# Incubadora_huevos.net
KiCad netlist of a schematic drawn in EAGLE
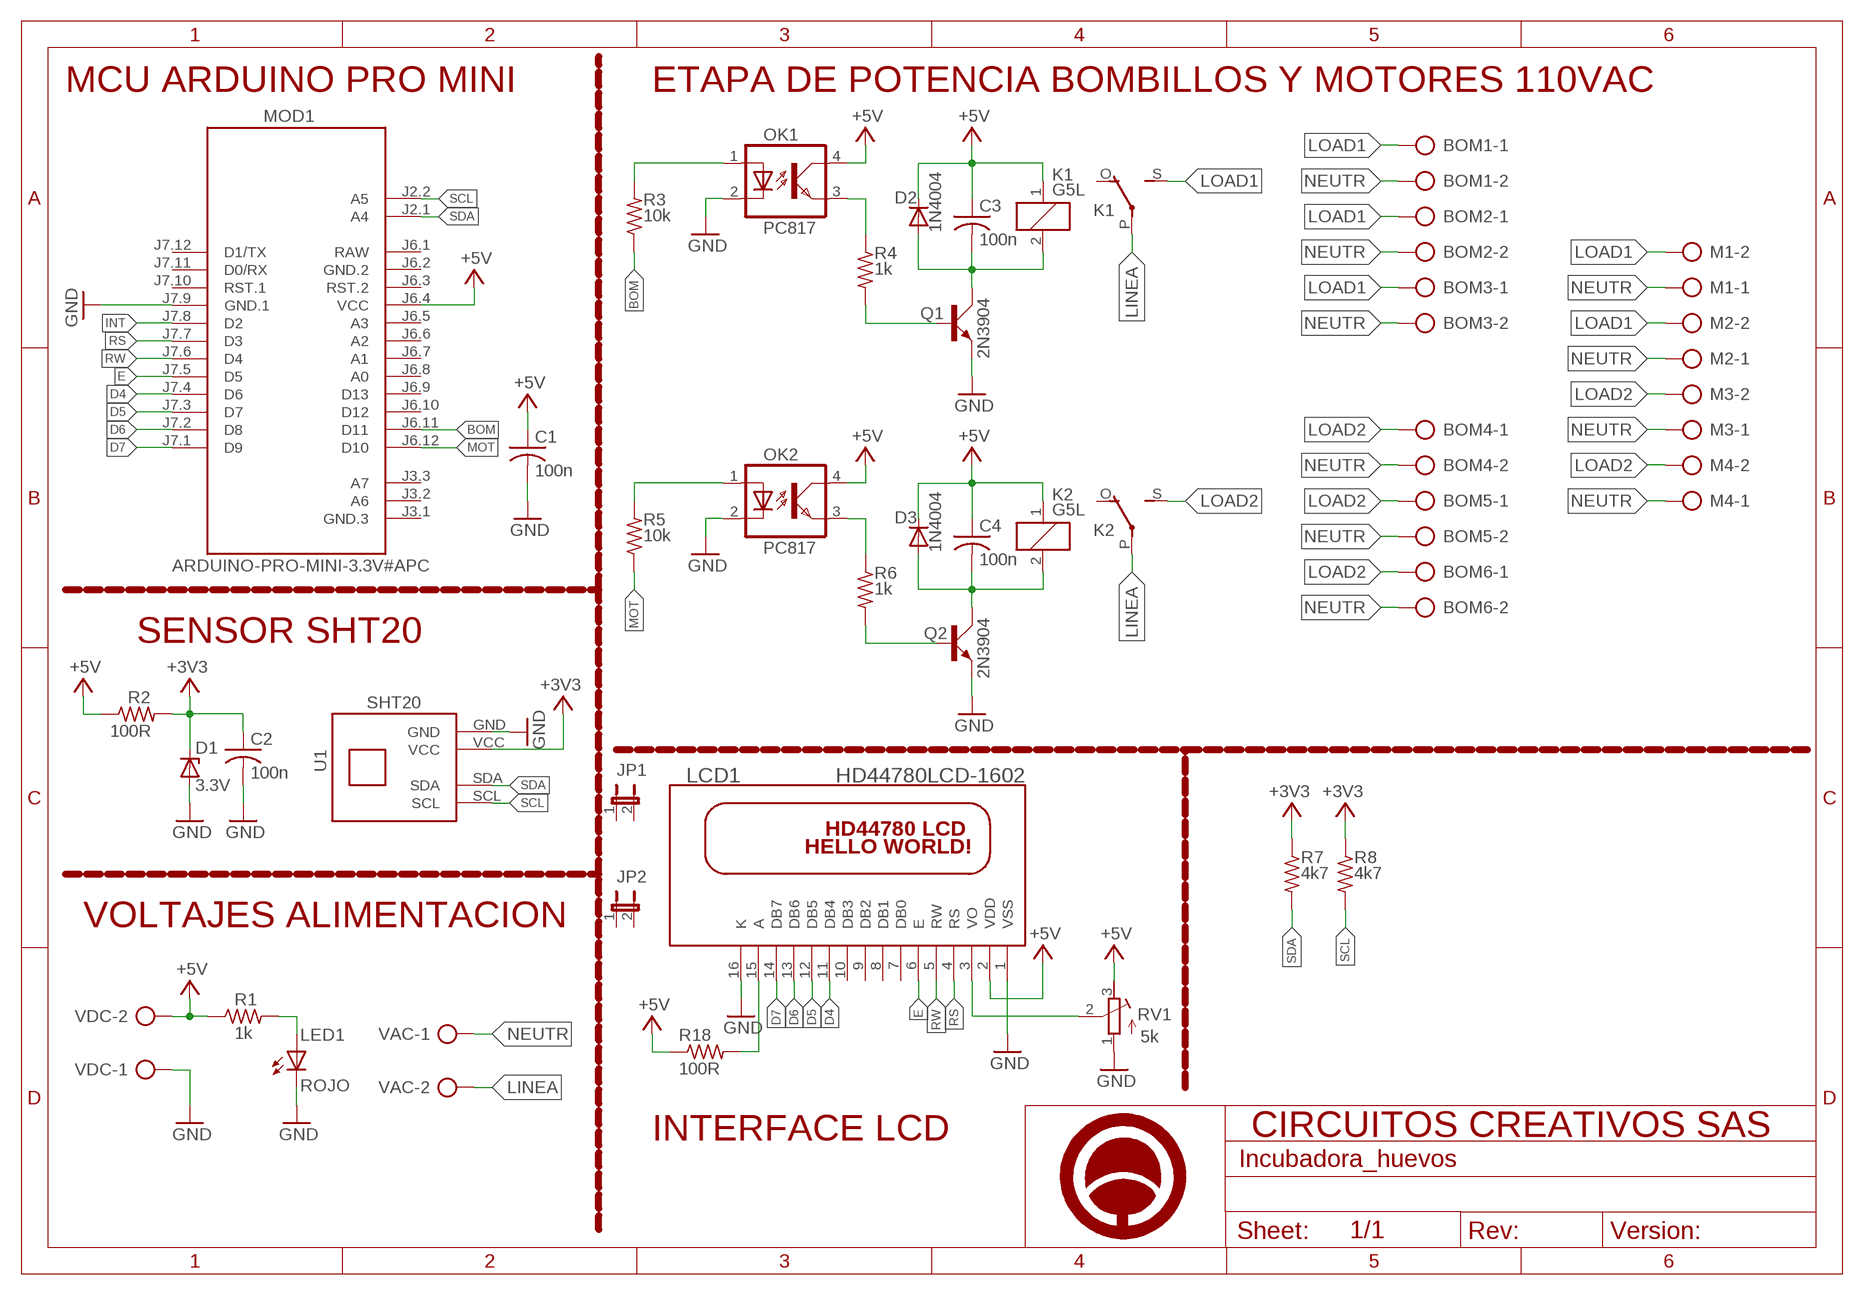
[diagram p0: schematic, sheet 1]

(export (version "E")
  (design (tool "Eeschema 10.0.6"))
  (components
    (comp (ref "BOM1")
      (value "AK500/2")
      (footprint "eagle-import:AK500_2")
      (libsource (lib "eagle-import") (part "AK500/2"))
    )
    (comp (ref "BOM2")
      (value "AK500/2")
      (footprint "eagle-import:AK500_2")
      (libsource (lib "eagle-import") (part "AK500/2"))
    )
    (comp (ref "BOM3")
      (value "AK500/2")
      (footprint "eagle-import:AK500_2")
      (libsource (lib "eagle-import") (part "AK500/2"))
    )
    (comp (ref "BOM4")
      (value "AK500/2")
      (footprint "eagle-import:AK500_2")
      (libsource (lib "eagle-import") (part "AK500/2"))
    )
    (comp (ref "BOM5")
      (value "AK500/2")
      (footprint "eagle-import:AK500_2")
      (libsource (lib "eagle-import") (part "AK500/2"))
    )
    (comp (ref "BOM6")
      (value "AK500/2")
      (footprint "eagle-import:AK500_2")
      (libsource (lib "eagle-import") (part "AK500/2"))
    )
    (comp (ref "C1")
      (value "100n")
      (footprint "eagle-import:C025-025X050")
      (libsource (lib "eagle-import") (part "C-US025-025X050"))
    )
    (comp (ref "C2")
      (value "100n")
      (footprint "eagle-import:C025-025X050")
      (libsource (lib "eagle-import") (part "C-US025-025X050"))
    )
    (comp (ref "C3")
      (value "100n")
      (footprint "eagle-import:C025-025X050")
      (libsource (lib "eagle-import") (part "C-US025-025X050"))
    )
    (comp (ref "C4")
      (value "100n")
      (footprint "eagle-import:C025-025X050")
      (libsource (lib "eagle-import") (part "C-US025-025X050"))
    )
    (comp (ref "D1")
      (value "3.3V")
      (footprint "eagle-import:DO41Z10")
      (libsource (lib "eagle-import") (part "ZENER-DIODEDO41Z10"))
    )
    (comp (ref "D2")
      (value "1N4004")
      (footprint "eagle-import:DO41-10")
      (libsource (lib "eagle-import") (part "1N4004"))
    )
    (comp (ref "D3")
      (value "1N4004")
      (footprint "eagle-import:DO41-10")
      (libsource (lib "eagle-import") (part "1N4004"))
    )
    (comp (ref "JP1")
      (value "JP1E")
      (footprint "eagle-import:JP1")
      (libsource (lib "eagle-import") (part "JP1E"))
    )
    (comp (ref "JP2")
      (value "JP1E")
      (footprint "eagle-import:JP1")
      (libsource (lib "eagle-import") (part "JP1E"))
    )
    (comp (ref "K1")
      (value "G5L")
      (footprint "eagle-import:G5LE")
      (libsource (lib "eagle-import") (part "G5L"))
    )
    (comp (ref "K2")
      (value "G5L")
      (footprint "eagle-import:G5LE")
      (libsource (lib "eagle-import") (part "G5L"))
    )
    (comp (ref "LCD1")
      (value "HD44780LCD-1602")
      (footprint "eagle-import:LCD1602")
      (libsource (lib "eagle-import") (part "HD44780LCD-1602"))
    )
    (comp (ref "LED1")
      (value "ROJO")
      (footprint "eagle-import:LED3MM")
      (libsource (lib "eagle-import") (part "LED3MM"))
    )
    (comp (ref "M1")
      (value "AK500/2")
      (footprint "eagle-import:AK500_2")
      (libsource (lib "eagle-import") (part "AK500/2"))
    )
    (comp (ref "M2")
      (value "AK500/2")
      (footprint "eagle-import:AK500_2")
      (libsource (lib "eagle-import") (part "AK500/2"))
    )
    (comp (ref "M3")
      (value "AK500/2")
      (footprint "eagle-import:AK500_2")
      (libsource (lib "eagle-import") (part "AK500/2"))
    )
    (comp (ref "M4")
      (value "AK500/2")
      (footprint "eagle-import:AK500_2")
      (libsource (lib "eagle-import") (part "AK500/2"))
    )
    (comp (ref "MOD1")
      (value "ARDUINO-PRO-MINI-3.3V#APC")
      (footprint "eagle-import:ARDUINO-PRO-MINI#APC")
      (libsource (lib "eagle-import") (part "ARDUINO-PRO-MINI-#APC3.3V"))
    )
    (comp (ref "OK1")
      (value "PC817")
      (footprint "eagle-import:DIL04")
      (fields (field (name "MPN") "PC817X4J000F"))
      (libsource (lib "eagle-import") (part "PC817"))
    )
    (comp (ref "OK2")
      (value "PC817")
      (footprint "eagle-import:DIL04")
      (fields (field (name "MPN") "PC817X4J000F"))
      (libsource (lib "eagle-import") (part "PC817"))
    )
    (comp (ref "Q1")
      (value "2N3904")
      (footprint "eagle-import:TO92D")
      (libsource (lib "eagle-import") (part "2N3904"))
    )
    (comp (ref "Q2")
      (value "2N3904")
      (footprint "eagle-import:TO92D")
      (libsource (lib "eagle-import") (part "2N3904"))
    )
    (comp (ref "R1")
      (value "1k")
      (footprint "eagle-import:0204_7")
      (libsource (lib "eagle-import") (part "R-US_0204/7"))
    )
    (comp (ref "R2")
      (value "100R")
      (footprint "eagle-import:0204_7")
      (libsource (lib "eagle-import") (part "R-US_0204/7"))
    )
    (comp (ref "R3")
      (value "10k")
      (footprint "eagle-import:0204_7")
      (libsource (lib "eagle-import") (part "R-US_0204/7"))
    )
    (comp (ref "R4")
      (value "1k")
      (footprint "eagle-import:0204_7")
      (libsource (lib "eagle-import") (part "R-US_0204/7"))
    )
    (comp (ref "R5")
      (value "10k")
      (footprint "eagle-import:0204_7")
      (libsource (lib "eagle-import") (part "R-US_0204/7"))
    )
    (comp (ref "R6")
      (value "1k")
      (footprint "eagle-import:0204_7")
      (libsource (lib "eagle-import") (part "R-US_0204/7"))
    )
    (comp (ref "R7")
      (value "4k7")
      (footprint "eagle-import:0204_7")
      (libsource (lib "eagle-import") (part "R-US_0204/7"))
    )
    (comp (ref "R8")
      (value "4k7")
      (footprint "eagle-import:0204_7")
      (libsource (lib "eagle-import") (part "R-US_0204/7"))
    )
    (comp (ref "R18")
      (value "100R")
      (footprint "eagle-import:0204_7")
      (libsource (lib "eagle-import") (part "R-US_0204/7"))
    )
    (comp (ref "RV1")
      (value "5k")
      (footprint "eagle-import:RTRIM3296W")
      (libsource (lib "eagle-import") (part "R-TRIMM3296W"))
    )
    (comp (ref "U$1")
      (value "A4_HORIZONTAL")
      (footprint "eagle-import:LOGO")
      (libsource (lib "eagle-import") (part "A4_HORIZONTAL"))
    )
    (comp (ref "U1")
      (value "SHT20")
      (footprint "eagle-import:SHT20")
      (libsource (lib "eagle-import") (part "SHT20"))
    )
    (comp (ref "VAC")
      (value "AK500/2")
      (footprint "eagle-import:AK500_2")
      (libsource (lib "eagle-import") (part "AK500/2"))
    )
    (comp (ref "VDC")
      (value "AK500/2")
      (footprint "eagle-import:AK500_2")
      (libsource (lib "eagle-import") (part "AK500/2"))
    )
  )
  (nets
    (net (code "1") (name "+3V3") (class "Default")
      (node (ref "C2") (pin "1") (pinfunction "1_1") (pintype "passive"))
      (node (ref "D1") (pin "C") (pinfunction "C_C") (pintype "passive"))
      (node (ref "R2") (pin "2") (pinfunction "2_2") (pintype "passive"))
      (node (ref "R7") (pin "1") (pinfunction "1_1") (pintype "passive"))
      (node (ref "R8") (pin "1") (pinfunction "1_1") (pintype "passive"))
      (node (ref "U1") (pin "VCC") (pinfunction "VCC_VCC") (pintype "power_in"))
    )
    (net (code "2") (name "+5V") (class "Default")
      (node (ref "C1") (pin "1") (pinfunction "1_1") (pintype "passive"))
      (node (ref "C3") (pin "1") (pinfunction "1_1") (pintype "passive"))
      (node (ref "C4") (pin "1") (pinfunction "1_1") (pintype "passive"))
      (node (ref "D2") (pin "C") (pinfunction "C_C") (pintype "passive"))
      (node (ref "D3") (pin "C") (pinfunction "C_C") (pintype "passive"))
      (node (ref "K1") (pin "1") (pinfunction "1_1") (pintype "passive"))
      (node (ref "K2") (pin "1") (pinfunction "1_1") (pintype "passive"))
      (node (ref "LCD1") (pin "2") (pinfunction "VDD_2") (pintype "power_in"))
      (node (ref "MOD1") (pin "J6.4") (pinfunction "VCC_J6.4") (pintype "power_in"))
      (node (ref "OK1") (pin "4") (pinfunction "COL_4") (pintype "passive"))
      (node (ref "OK2") (pin "4") (pinfunction "COL_4") (pintype "passive"))
      (node (ref "R1") (pin "1") (pinfunction "1_1") (pintype "passive"))
      (node (ref "R18") (pin "1") (pinfunction "1_1") (pintype "passive"))
      (node (ref "R2") (pin "1") (pinfunction "1_1") (pintype "passive"))
      (node (ref "RV1") (pin "3") (pinfunction "E_3") (pintype "passive"))
      (node (ref "VDC") (pin "2") (pinfunction "KL_2") (pintype "passive"))
    )
    (net (code "3") (name "/GND.2") (class "Default")
      (node (ref "MOD1") (pin "J6.2") (pinfunction "GND.2_J6.2") (pintype "power_in"))
    )
    (net (code "4") (name "/RAW") (class "Default")
      (node (ref "MOD1") (pin "J6.1") (pinfunction "RAW_J6.1") (pintype "power_in"))
    )
    (net (code "5") (name "BOM") (class "Default")
      (node (ref "MOD1") (pin "J6.11") (pinfunction "D11_J6.11") (pintype "bidirectional"))
      (node (ref "R3") (pin "1") (pinfunction "1_1") (pintype "passive"))
    )
    (net (code "6") (name "D4") (class "Default")
      (node (ref "LCD1") (pin "11") (pinfunction "DB4_11") (pintype "bidirectional"))
      (node (ref "MOD1") (pin "J7.4") (pinfunction "D6_J7.4") (pintype "bidirectional"))
    )
    (net (code "7") (name "D5") (class "Default")
      (node (ref "LCD1") (pin "12") (pinfunction "DB5_12") (pintype "bidirectional"))
      (node (ref "MOD1") (pin "J7.3") (pinfunction "D7_J7.3") (pintype "bidirectional"))
    )
    (net (code "8") (name "D6") (class "Default")
      (node (ref "LCD1") (pin "13") (pinfunction "DB6_13") (pintype "bidirectional"))
      (node (ref "MOD1") (pin "J7.2") (pinfunction "D8_J7.2") (pintype "bidirectional"))
    )
    (net (code "9") (name "D7") (class "Default")
      (node (ref "LCD1") (pin "14") (pinfunction "DB7_14") (pintype "bidirectional"))
      (node (ref "MOD1") (pin "J7.1") (pinfunction "D9_J7.1") (pintype "bidirectional"))
    )
    (net (code "10") (name "E") (class "Default")
      (node (ref "LCD1") (pin "6") (pinfunction "E_6") (pintype "input"))
      (node (ref "MOD1") (pin "J7.5") (pinfunction "D5_J7.5") (pintype "bidirectional"))
    )
    (net (code "11") (name "GND") (class "Default")
      (node (ref "C1") (pin "2") (pinfunction "2_2") (pintype "passive"))
      (node (ref "C2") (pin "2") (pinfunction "2_2") (pintype "passive"))
      (node (ref "D1") (pin "A") (pinfunction "A_A") (pintype "passive"))
      (node (ref "LCD1") (pin "1") (pinfunction "VSS_1") (pintype "power_in"))
      (node (ref "LCD1") (pin "16") (pinfunction "K_16") (pintype "input"))
      (node (ref "LED1") (pin "K") (pinfunction "C_K") (pintype "passive"))
      (node (ref "MOD1") (pin "J7.9") (pinfunction "GND.1_J7.9") (pintype "power_in"))
      (node (ref "OK1") (pin "2") (pinfunction "C_2") (pintype "passive"))
      (node (ref "OK2") (pin "2") (pinfunction "C_2") (pintype "passive"))
      (node (ref "Q1") (pin "E") (pinfunction "E_E") (pintype "passive"))
      (node (ref "Q2") (pin "E") (pinfunction "E_E") (pintype "passive"))
      (node (ref "RV1") (pin "1") (pinfunction "A_1") (pintype "passive"))
      (node (ref "U1") (pin "GND") (pinfunction "GND_GND") (pintype "power_in"))
      (node (ref "VDC") (pin "1") (pinfunction "KL_1") (pintype "passive"))
    )
    (net (code "12") (name "INT") (class "Default")
      (node (ref "MOD1") (pin "J7.8") (pinfunction "D2_J7.8") (pintype "bidirectional"))
    )
    (net (code "13") (name "LINEA") (class "Default")
      (node (ref "K1") (pin "P") (pinfunction "P_P") (pintype "passive"))
      (node (ref "K2") (pin "P") (pinfunction "P_P") (pintype "passive"))
      (node (ref "VAC") (pin "2") (pinfunction "KL_2") (pintype "passive"))
    )
    (net (code "14") (name "LOAD1") (class "Default")
      (node (ref "BOM1") (pin "1") (pinfunction "KL_1") (pintype "passive"))
      (node (ref "BOM2") (pin "1") (pinfunction "KL_1") (pintype "passive"))
      (node (ref "BOM3") (pin "1") (pinfunction "KL_1") (pintype "passive"))
      (node (ref "K1") (pin "S") (pinfunction "S_S") (pintype "passive"))
      (node (ref "M1") (pin "2") (pinfunction "KL_2") (pintype "passive"))
      (node (ref "M2") (pin "2") (pinfunction "KL_2") (pintype "passive"))
    )
    (net (code "15") (name "LOAD2") (class "Default")
      (node (ref "BOM4") (pin "1") (pinfunction "KL_1") (pintype "passive"))
      (node (ref "BOM5") (pin "1") (pinfunction "KL_1") (pintype "passive"))
      (node (ref "BOM6") (pin "1") (pinfunction "KL_1") (pintype "passive"))
      (node (ref "K2") (pin "S") (pinfunction "S_S") (pintype "passive"))
      (node (ref "M3") (pin "2") (pinfunction "KL_2") (pintype "passive"))
      (node (ref "M4") (pin "2") (pinfunction "KL_2") (pintype "passive"))
    )
    (net (code "16") (name "MOT") (class "Default")
      (node (ref "MOD1") (pin "J6.12") (pinfunction "D10_J6.12") (pintype "bidirectional"))
      (node (ref "R5") (pin "1") (pinfunction "1_1") (pintype "passive"))
    )
    (net (code "17") (name "NEUTR") (class "Default")
      (node (ref "BOM1") (pin "2") (pinfunction "KL_2") (pintype "passive"))
      (node (ref "BOM2") (pin "2") (pinfunction "KL_2") (pintype "passive"))
      (node (ref "BOM3") (pin "2") (pinfunction "KL_2") (pintype "passive"))
      (node (ref "BOM4") (pin "2") (pinfunction "KL_2") (pintype "passive"))
      (node (ref "BOM5") (pin "2") (pinfunction "KL_2") (pintype "passive"))
      (node (ref "BOM6") (pin "2") (pinfunction "KL_2") (pintype "passive"))
      (node (ref "M1") (pin "1") (pinfunction "KL_1") (pintype "passive"))
      (node (ref "M2") (pin "1") (pinfunction "KL_1") (pintype "passive"))
      (node (ref "M3") (pin "1") (pinfunction "KL_1") (pintype "passive"))
      (node (ref "M4") (pin "1") (pinfunction "KL_1") (pintype "passive"))
      (node (ref "VAC") (pin "1") (pinfunction "KL_1") (pintype "passive"))
    )
    (net (code "18") (name "Net-(C3-Pad2)") (class "Default")
      (node (ref "C3") (pin "2") (pinfunction "2_2") (pintype "passive"))
      (node (ref "D2") (pin "A") (pinfunction "A_A") (pintype "passive"))
      (node (ref "K1") (pin "2") (pinfunction "2_2") (pintype "passive"))
      (node (ref "Q1") (pin "C") (pinfunction "C_C") (pintype "passive"))
    )
    (net (code "19") (name "Net-(C4-Pad2)") (class "Default")
      (node (ref "C4") (pin "2") (pinfunction "2_2") (pintype "passive"))
      (node (ref "D3") (pin "A") (pinfunction "A_A") (pintype "passive"))
      (node (ref "K2") (pin "2") (pinfunction "2_2") (pintype "passive"))
      (node (ref "Q2") (pin "C") (pinfunction "C_C") (pintype "passive"))
    )
    (net (code "20") (name "Net-(LCD1-A)") (class "Default")
      (node (ref "LCD1") (pin "15") (pinfunction "A_15") (pintype "input"))
      (node (ref "R18") (pin "2") (pinfunction "2_2") (pintype "passive"))
    )
    (net (code "21") (name "Net-(LCD1-VO)") (class "Default")
      (node (ref "LCD1") (pin "3") (pinfunction "VO_3") (pintype "input"))
      (node (ref "RV1") (pin "2") (pinfunction "S_2") (pintype "passive"))
    )
    (net (code "22") (name "Net-(LED1-PadA)") (class "Default")
      (node (ref "LED1") (pin "A") (pinfunction "A_A") (pintype "passive"))
      (node (ref "R1") (pin "2") (pinfunction "2_2") (pintype "passive"))
    )
    (net (code "23") (name "Net-(OK1-A)") (class "Default")
      (node (ref "OK1") (pin "1") (pinfunction "A_1") (pintype "passive"))
      (node (ref "R3") (pin "2") (pinfunction "2_2") (pintype "passive"))
    )
    (net (code "24") (name "Net-(OK1-EMIT)") (class "Default")
      (node (ref "OK1") (pin "3") (pinfunction "EMIT_3") (pintype "passive"))
      (node (ref "R4") (pin "1") (pinfunction "1_1") (pintype "passive"))
    )
    (net (code "25") (name "Net-(OK2-A)") (class "Default")
      (node (ref "OK2") (pin "1") (pinfunction "A_1") (pintype "passive"))
      (node (ref "R5") (pin "2") (pinfunction "2_2") (pintype "passive"))
    )
    (net (code "26") (name "Net-(OK2-EMIT)") (class "Default")
      (node (ref "OK2") (pin "3") (pinfunction "EMIT_3") (pintype "passive"))
      (node (ref "R6") (pin "1") (pinfunction "1_1") (pintype "passive"))
    )
    (net (code "27") (name "Net-(Q1-PadB)") (class "Default")
      (node (ref "Q1") (pin "B") (pinfunction "B_B") (pintype "passive"))
      (node (ref "R4") (pin "2") (pinfunction "2_2") (pintype "passive"))
    )
    (net (code "28") (name "Net-(Q2-PadB)") (class "Default")
      (node (ref "Q2") (pin "B") (pinfunction "B_B") (pintype "passive"))
      (node (ref "R6") (pin "2") (pinfunction "2_2") (pintype "passive"))
    )
    (net (code "29") (name "RS") (class "Default")
      (node (ref "LCD1") (pin "4") (pinfunction "RS_4") (pintype "input"))
      (node (ref "MOD1") (pin "J7.7") (pinfunction "D3_J7.7") (pintype "bidirectional"))
    )
    (net (code "30") (name "RW") (class "Default")
      (node (ref "LCD1") (pin "5") (pinfunction "RW_5") (pintype "input"))
      (node (ref "MOD1") (pin "J7.6") (pinfunction "D4_J7.6") (pintype "bidirectional"))
    )
    (net (code "31") (name "SCL") (class "Default")
      (node (ref "MOD1") (pin "J2.2") (pinfunction "A5_J2.2") (pintype "bidirectional"))
      (node (ref "R8") (pin "2") (pinfunction "2_2") (pintype "passive"))
      (node (ref "U1") (pin "SCL") (pinfunction "SCL_SCL") (pintype "bidirectional"))
    )
    (net (code "32") (name "SDA") (class "Default")
      (node (ref "MOD1") (pin "J2.1") (pinfunction "A4_J2.1") (pintype "bidirectional"))
      (node (ref "R7") (pin "2") (pinfunction "2_2") (pintype "passive"))
      (node (ref "U1") (pin "SDA") (pinfunction "SDA_SDA") (pintype "bidirectional"))
    )
    (net (code "33") (name "unconnected-(JP1-Pad1)") (class "Default")
      (node (ref "JP1") (pin "1") (pinfunction "1_1") (pintype "passive"))
    )
    (net (code "34") (name "unconnected-(JP1-Pad2)") (class "Default")
      (node (ref "JP1") (pin "2") (pinfunction "2_2") (pintype "passive"))
    )
    (net (code "35") (name "unconnected-(JP2-Pad1)") (class "Default")
      (node (ref "JP2") (pin "1") (pinfunction "1_1") (pintype "passive"))
    )
    (net (code "36") (name "unconnected-(JP2-Pad2)") (class "Default")
      (node (ref "JP2") (pin "2") (pinfunction "2_2") (pintype "passive"))
    )
    (net (code "37") (name "unconnected-(K1-PadO)") (class "Default")
      (node (ref "K1") (pin "O") (pinfunction "O_O") (pintype "passive"))
    )
    (net (code "38") (name "unconnected-(K2-PadO)") (class "Default")
      (node (ref "K2") (pin "O") (pinfunction "O_O") (pintype "passive"))
    )
    (net (code "39") (name "unconnected-(LCD1-DB0-Pad7)") (class "Default")
      (node (ref "LCD1") (pin "7") (pinfunction "DB0_7") (pintype "bidirectional"))
    )
    (net (code "40") (name "unconnected-(LCD1-DB1-Pad8)") (class "Default")
      (node (ref "LCD1") (pin "8") (pinfunction "DB1_8") (pintype "bidirectional"))
    )
    (net (code "41") (name "unconnected-(LCD1-DB2-Pad9)") (class "Default")
      (node (ref "LCD1") (pin "9") (pinfunction "DB2_9") (pintype "bidirectional"))
    )
    (net (code "42") (name "unconnected-(LCD1-DB3-Pad10)") (class "Default")
      (node (ref "LCD1") (pin "10") (pinfunction "DB3_10") (pintype "bidirectional"))
    )
    (net (code "43") (name "unconnected-(MOD1-A0-PadJ6.8)") (class "Default")
      (node (ref "MOD1") (pin "J6.8") (pinfunction "A0_J6.8") (pintype "bidirectional"))
    )
    (net (code "44") (name "unconnected-(MOD1-A1-PadJ6.7)") (class "Default")
      (node (ref "MOD1") (pin "J6.7") (pinfunction "A1_J6.7") (pintype "bidirectional"))
    )
    (net (code "45") (name "unconnected-(MOD1-A2-PadJ6.6)") (class "Default")
      (node (ref "MOD1") (pin "J6.6") (pinfunction "A2_J6.6") (pintype "bidirectional"))
    )
    (net (code "46") (name "unconnected-(MOD1-A3-PadJ6.5)") (class "Default")
      (node (ref "MOD1") (pin "J6.5") (pinfunction "A3_J6.5") (pintype "bidirectional"))
    )
    (net (code "47") (name "unconnected-(MOD1-A6-PadJ3.2)") (class "Default")
      (node (ref "MOD1") (pin "J3.2") (pinfunction "A6_J3.2") (pintype "bidirectional"))
    )
    (net (code "48") (name "unconnected-(MOD1-A7-PadJ3.3)") (class "Default")
      (node (ref "MOD1") (pin "J3.3") (pinfunction "A7_J3.3") (pintype "bidirectional"))
    )
    (net (code "49") (name "unconnected-(MOD1-D0{slash}RX-PadJ7.11)") (class "Default")
      (node (ref "MOD1") (pin "J7.11") (pinfunction "D0/RX_J7.11") (pintype "bidirectional"))
    )
    (net (code "50") (name "unconnected-(MOD1-D1{slash}TX-PadJ7.12)") (class "Default")
      (node (ref "MOD1") (pin "J7.12") (pinfunction "D1/TX_J7.12") (pintype "bidirectional"))
    )
    (net (code "51") (name "unconnected-(MOD1-D12-PadJ6.10)") (class "Default")
      (node (ref "MOD1") (pin "J6.10") (pinfunction "D12_J6.10") (pintype "bidirectional"))
    )
    (net (code "52") (name "unconnected-(MOD1-D13-PadJ6.9)") (class "Default")
      (node (ref "MOD1") (pin "J6.9") (pinfunction "D13_J6.9") (pintype "bidirectional"))
    )
    (net (code "53") (name "unconnected-(MOD1-GND.3-PadJ3.1)") (class "Default")
      (node (ref "MOD1") (pin "J3.1") (pinfunction "GND.3_J3.1") (pintype "bidirectional"))
    )
    (net (code "54") (name "unconnected-(MOD1-RST.1-PadJ7.10)") (class "Default")
      (node (ref "MOD1") (pin "J7.10") (pinfunction "RST.1_J7.10") (pintype "bidirectional"))
    )
    (net (code "55") (name "unconnected-(MOD1-RST.2-PadJ6.3)") (class "Default")
      (node (ref "MOD1") (pin "J6.3") (pinfunction "RST.2_J6.3") (pintype "bidirectional"))
    )
  )
)
